# vi.net
KiCad netlist of a schematic drawn in Altium Designer
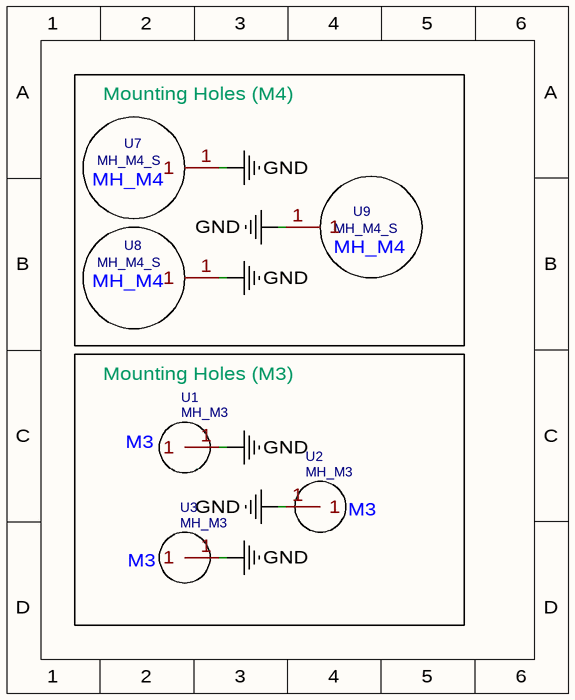
[diagram p0: vi.schdoc]

(export (version "E")
  (design (tool "Eeschema 10.0.6"))
  (components
    (comp (ref "U1")
      (value "MH_M3")
      (fields (field (name "CONTRIBUTOR") "js314dev"))
      (libsource (lib "altium-import") (part "root_0_MH_M3_"))
    )
    (comp (ref "U2")
      (value "MH_M3")
      (fields (field (name "CONTRIBUTOR") "js314dev"))
      (libsource (lib "altium-import") (part "root_2_MH_M3_"))
    )
    (comp (ref "U3")
      (value "MH_M3")
      (fields (field (name "CONTRIBUTOR") "js314dev"))
      (libsource (lib "altium-import") (part "root_0_MH_M3_"))
    )
    (comp (ref "U7")
      (value "MH_M4_S")
      (fields (field (name "CONTRIBUTOR") "js314dev"))
      (libsource (lib "altium-import") (part "root_0_MH_M4_S_"))
    )
    (comp (ref "U8")
      (value "MH_M4_S")
      (fields (field (name "CONTRIBUTOR") "js314dev"))
      (libsource (lib "altium-import") (part "root_0_MH_M4_S_"))
    )
    (comp (ref "U9")
      (value "MH_M4_S")
      (fields (field (name "CONTRIBUTOR") "js314dev"))
      (libsource (lib "altium-import") (part "root_2_MH_M4_S_"))
    )
  )
  (nets
    (net (code "1") (name "GND") (class "Default")
      (node (ref "U1") (pin "1") (pinfunction "1_1") (pintype "passive"))
      (node (ref "U2") (pin "1") (pinfunction "1_1") (pintype "passive"))
      (node (ref "U3") (pin "1") (pinfunction "1_1") (pintype "passive"))
      (node (ref "U7") (pin "1") (pinfunction "1_1") (pintype "passive"))
      (node (ref "U8") (pin "1") (pinfunction "1_1") (pintype "passive"))
      (node (ref "U9") (pin "1") (pinfunction "1_1") (pintype "passive"))
    )
  )
)
